# microbit-v2-smart-robot-schematic-diagra.net
KiCad netlist of a schematic drawn in EasyEDA
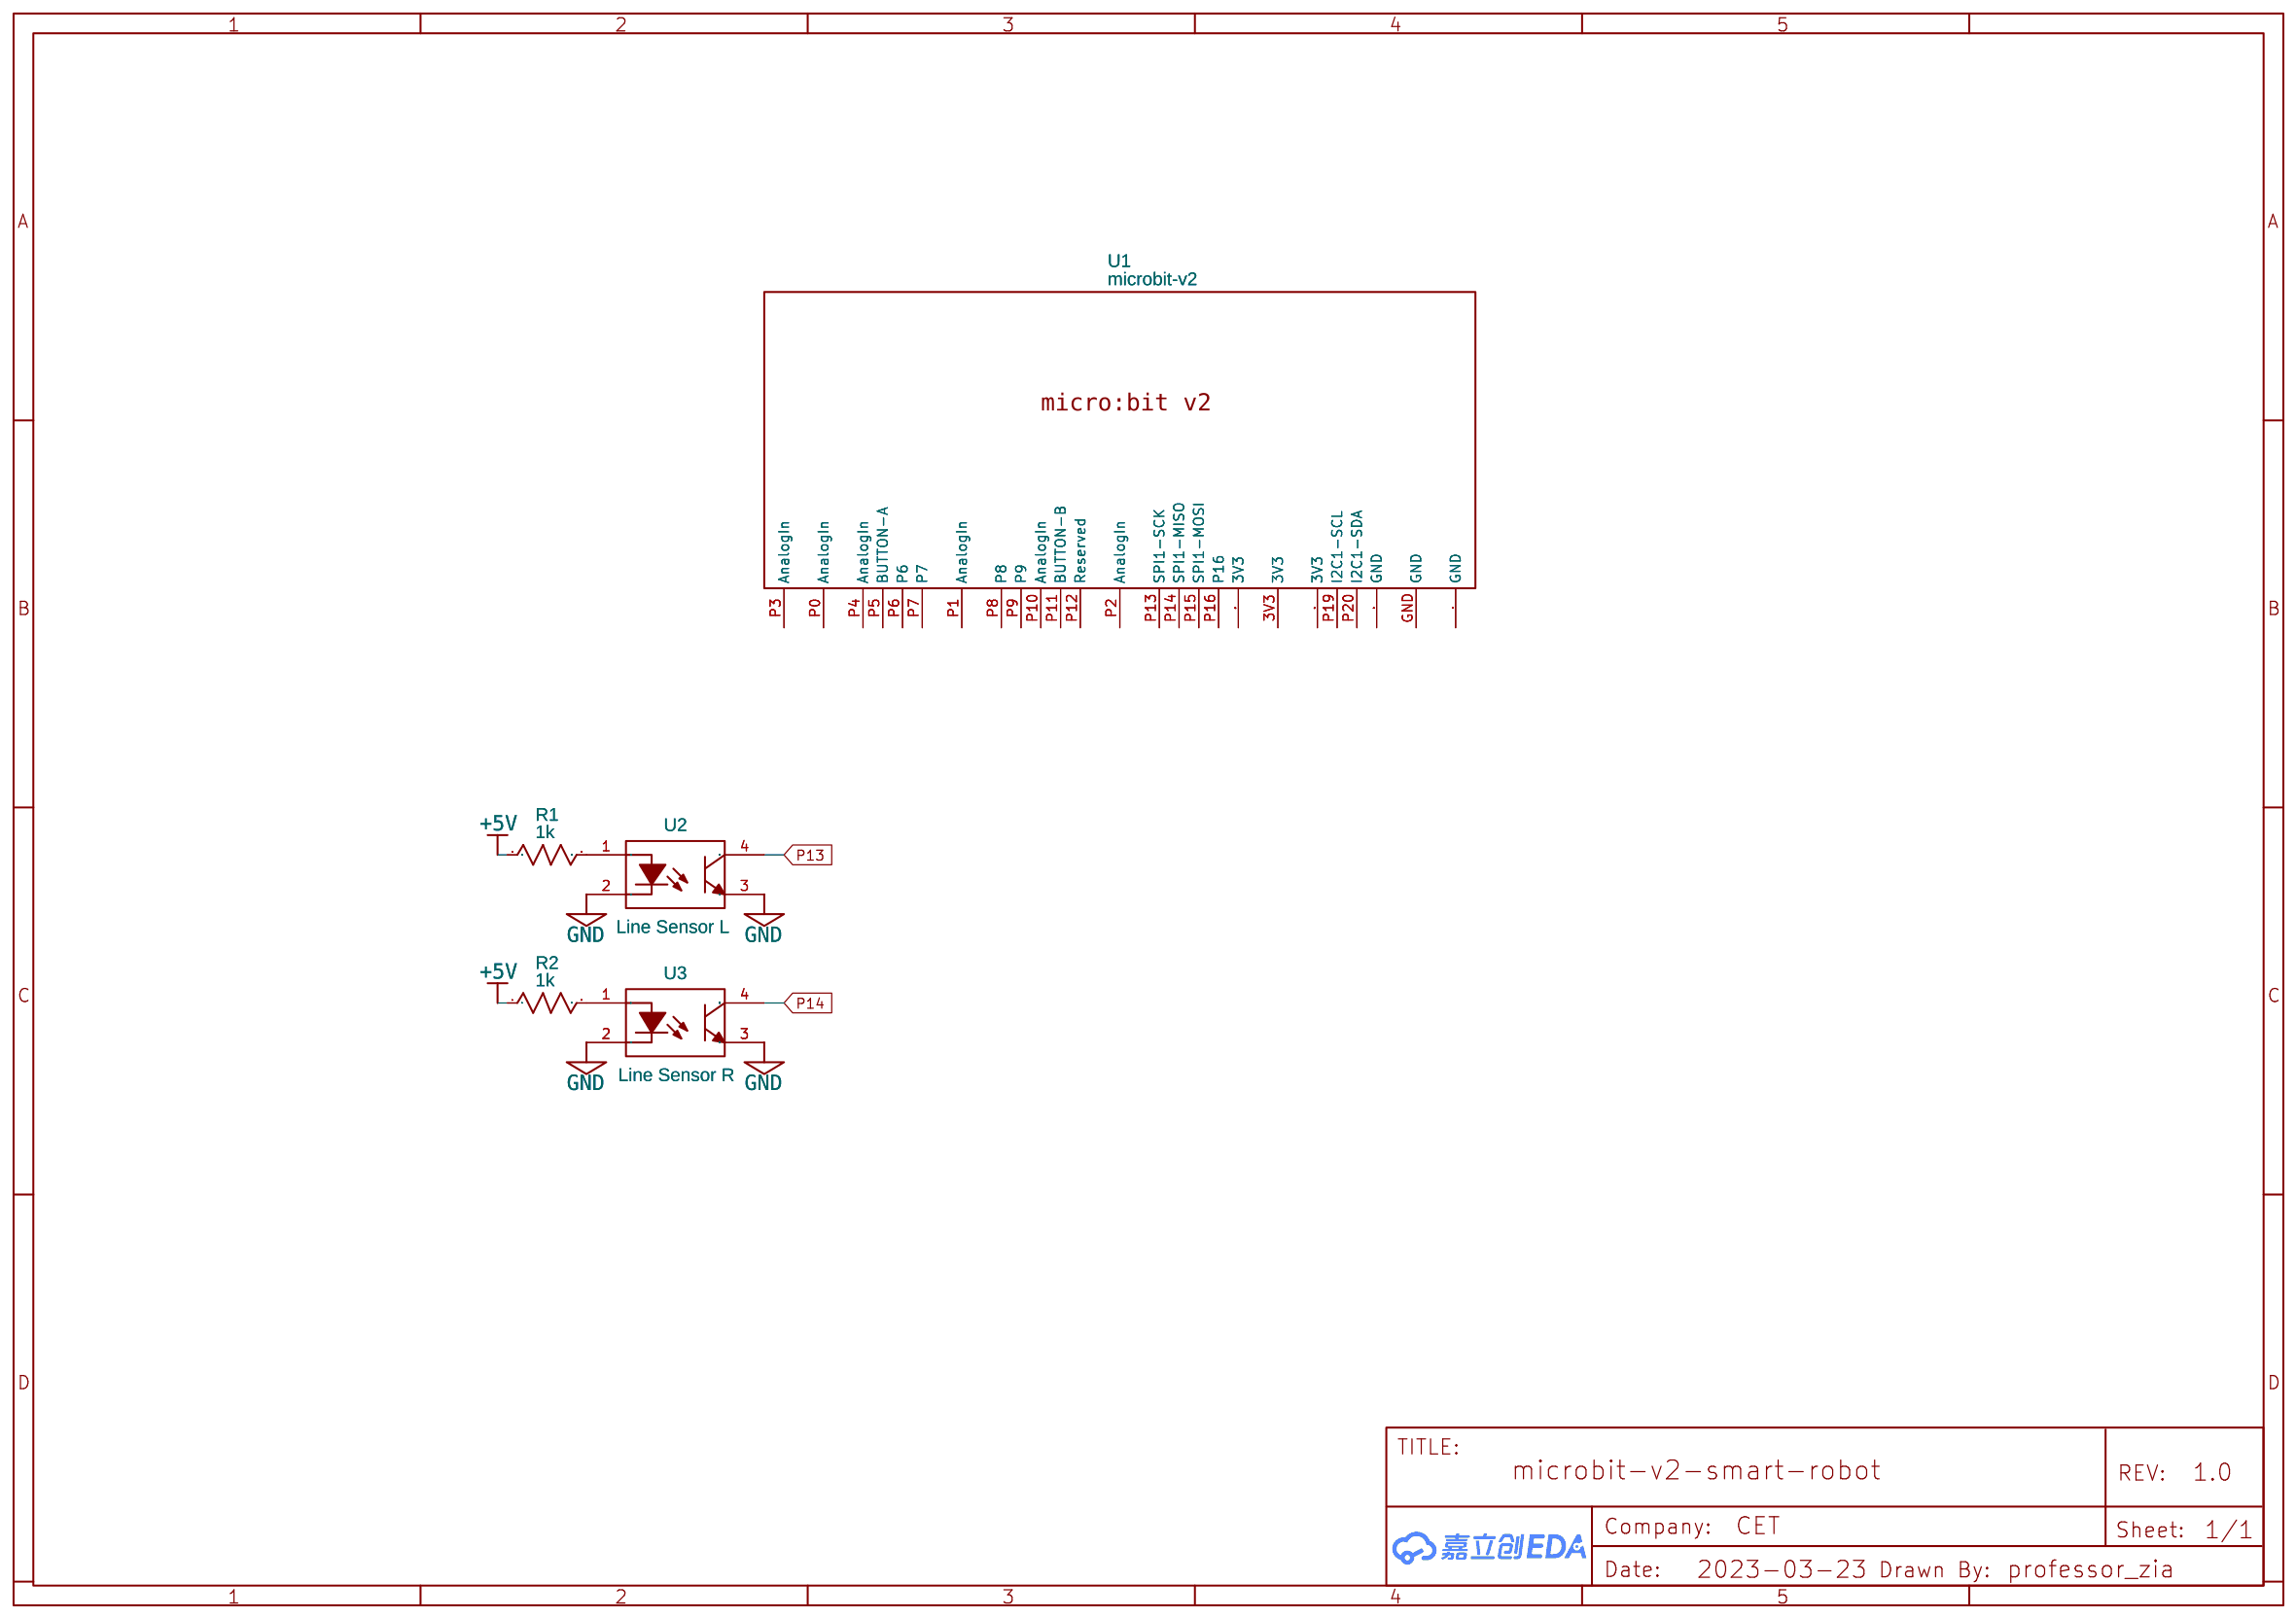
[diagram p0: schematic sheet]

(export (version "E")
  (design (tool "Eeschema 10.0.6"))
  (components
    (comp (ref "R1") (value "1k") (libsource (lib "") (part "R_0603_US")))
    (comp (ref "R2") (value "1k") (libsource (lib "") (part "R_0603_US")))
    (comp (ref "U1") (value "microbit-v2") (libsource (lib "") (part "microbit-v2")))
    (comp (ref "U2")
      (value "Line Sensor L")
      (fields
        (field (name "BOM_Manufacturer Part") "TLP291(GB-TP,SE(O")
        (field (name "BOM_Supplier Part") "C393895")
      )
      (libsource (lib "") (part "TLP291(GB-TP,SE(O"))
    )
    (comp (ref "U3")
      (value "Line Sensor R")
      (fields
        (field (name "BOM_Manufacturer Part") "TLP291(GB-TP,SE(O")
        (field (name "BOM_Supplier Part") "C393895")
      )
      (libsource (lib "") (part "TLP291(GB-TP,SE(O"))
    )
  )
  (nets
    (net (code "1") (name "+5V") (class "Default")
      (node (ref "R1") (pin "1") (pinfunction "1_1") (pintype "unspecified"))
      (node (ref "R2") (pin "1") (pinfunction "1_1") (pintype "unspecified"))
    )
    (net (code "2") (name "GND") (class "Default")
      (node (ref "U2") (pin "2") (pinfunction "CAT_2") (pintype "unspecified"))
      (node (ref "U2") (pin "3") (pinfunction "EM_3") (pintype "unspecified"))
      (node (ref "U3") (pin "2") (pinfunction "CAT_2") (pintype "unspecified"))
      (node (ref "U3") (pin "3") (pinfunction "EM_3") (pintype "unspecified"))
    )
    (net (code "3") (name "Net-(U2-AN)") (class "Default")
      (node (ref "R1") (pin "2") (pinfunction "2_2") (pintype "unspecified"))
      (node (ref "U2") (pin "1") (pinfunction "AN_1") (pintype "unspecified"))
    )
    (net (code "4") (name "Net-(U3-AN)") (class "Default")
      (node (ref "R2") (pin "2") (pinfunction "2_2") (pintype "unspecified"))
      (node (ref "U3") (pin "1") (pinfunction "AN_1") (pintype "unspecified"))
    )
    (net (code "5") (name "P13") (class "Default")
      (node (ref "U2") (pin "4") (pinfunction "COL_4") (pintype "unspecified"))
    )
    (net (code "6") (name "P14") (class "Default")
      (node (ref "U3") (pin "4") (pinfunction "COL_4") (pintype "unspecified"))
    )
    (net (code "7") (name "unconnected-(U1-3V3-Pad3Va)") (class "Default")
      (node (ref "U1") (pin "3Va") (pinfunction "3V3_3Va") (pintype "unspecified"))
    )
    (net (code "8") (name "unconnected-(U1-3V3-Pad3Vb)") (class "Default")
      (node (ref "U1") (pin "3Vb") (pinfunction "3V3_3Vb") (pintype "unspecified"))
    )
    (net (code "9") (name "unconnected-(U1-AnalogIn-PadP0)") (class "Default")
      (node (ref "U1") (pin "P0") (pinfunction "AnalogIn_P0") (pintype "unspecified"))
    )
    (net (code "10") (name "unconnected-(U1-AnalogIn-PadP1)") (class "Default")
      (node (ref "U1") (pin "P1") (pinfunction "AnalogIn_P1") (pintype "unspecified"))
    )
    (net (code "11") (name "unconnected-(U1-AnalogIn-PadP2)") (class "Default")
      (node (ref "U1") (pin "P2") (pinfunction "AnalogIn_P2") (pintype "unspecified"))
    )
    (net (code "12") (name "unconnected-(U1-AnalogIn-PadP3)") (class "Default")
      (node (ref "U1") (pin "P3") (pinfunction "AnalogIn_P3") (pintype "unspecified"))
    )
    (net (code "13") (name "unconnected-(U1-AnalogIn-PadP4)") (class "Default")
      (node (ref "U1") (pin "P4") (pinfunction "AnalogIn_P4") (pintype "unspecified"))
    )
    (net (code "14") (name "unconnected-(U1-AnalogIn-PadP10)") (class "Default")
      (node (ref "U1") (pin "P10") (pinfunction "AnalogIn_P10") (pintype "unspecified"))
    )
    (net (code "15") (name "unconnected-(U1-BUTTON-A-PadP5)") (class "Default")
      (node (ref "U1") (pin "P5") (pinfunction "BUTTON-A_P5") (pintype "unspecified"))
    )
    (net (code "16") (name "unconnected-(U1-BUTTON-B-PadP11)") (class "Default")
      (node (ref "U1") (pin "P11") (pinfunction "BUTTON-B_P11") (pintype "unspecified"))
    )
    (net (code "17") (name "unconnected-(U1-GND-PadGa)") (class "Default")
      (node (ref "U1") (pin "Ga") (pinfunction "GND_Ga") (pintype "unspecified"))
    )
    (net (code "18") (name "unconnected-(U1-GND-PadGb)") (class "Default")
      (node (ref "U1") (pin "Gb") (pinfunction "GND_Gb") (pintype "unspecified"))
    )
    (net (code "19") (name "unconnected-(U1-I2C1-SCL-PadP19)") (class "Default")
      (node (ref "U1") (pin "P19") (pinfunction "I2C1-SCL_P19") (pintype "unspecified"))
    )
    (net (code "20") (name "unconnected-(U1-I2C1-SDA-PadP20)") (class "Default")
      (node (ref "U1") (pin "P20") (pinfunction "I2C1-SDA_P20") (pintype "unspecified"))
    )
    (net (code "21") (name "unconnected-(U1-Pad3V3)") (class "Default")
      (node (ref "U1") (pin "3V3") (pinfunction "3V3_3V3") (pintype "unspecified"))
    )
    (net (code "22") (name "unconnected-(U1-PadGND)") (class "Default")
      (node (ref "U1") (pin "GND") (pinfunction "GND_GND") (pintype "unspecified"))
    )
    (net (code "23") (name "unconnected-(U1-PadP6)") (class "Default")
      (node (ref "U1") (pin "P6") (pinfunction "P6_P6") (pintype "unspecified"))
    )
    (net (code "24") (name "unconnected-(U1-PadP7)") (class "Default")
      (node (ref "U1") (pin "P7") (pinfunction "P7_P7") (pintype "unspecified"))
    )
    (net (code "25") (name "unconnected-(U1-PadP8)") (class "Default")
      (node (ref "U1") (pin "P8") (pinfunction "P8_P8") (pintype "unspecified"))
    )
    (net (code "26") (name "unconnected-(U1-PadP9)") (class "Default")
      (node (ref "U1") (pin "P9") (pinfunction "P9_P9") (pintype "unspecified"))
    )
    (net (code "27") (name "unconnected-(U1-PadP16)") (class "Default")
      (node (ref "U1") (pin "P16") (pinfunction "P16_P16") (pintype "unspecified"))
    )
    (net (code "28") (name "unconnected-(U1-Reserved-PadP12)") (class "Default")
      (node (ref "U1") (pin "P12") (pinfunction "Reserved_P12") (pintype "unspecified"))
    )
    (net (code "29") (name "unconnected-(U1-SPI1-MISO-PadP14)") (class "Default")
      (node (ref "U1") (pin "P14") (pinfunction "SPI1-MISO_P14") (pintype "unspecified"))
    )
    (net (code "30") (name "unconnected-(U1-SPI1-MOSI-PadP15)") (class "Default")
      (node (ref "U1") (pin "P15") (pinfunction "SPI1-MOSI_P15") (pintype "unspecified"))
    )
    (net (code "31") (name "unconnected-(U1-SPI1-SCK-PadP13)") (class "Default")
      (node (ref "U1") (pin "P13") (pinfunction "SPI1-SCK_P13") (pintype "unspecified"))
    )
  )
)
